# Power.net
KiCad netlist of a schematic drawn in Altium Designer
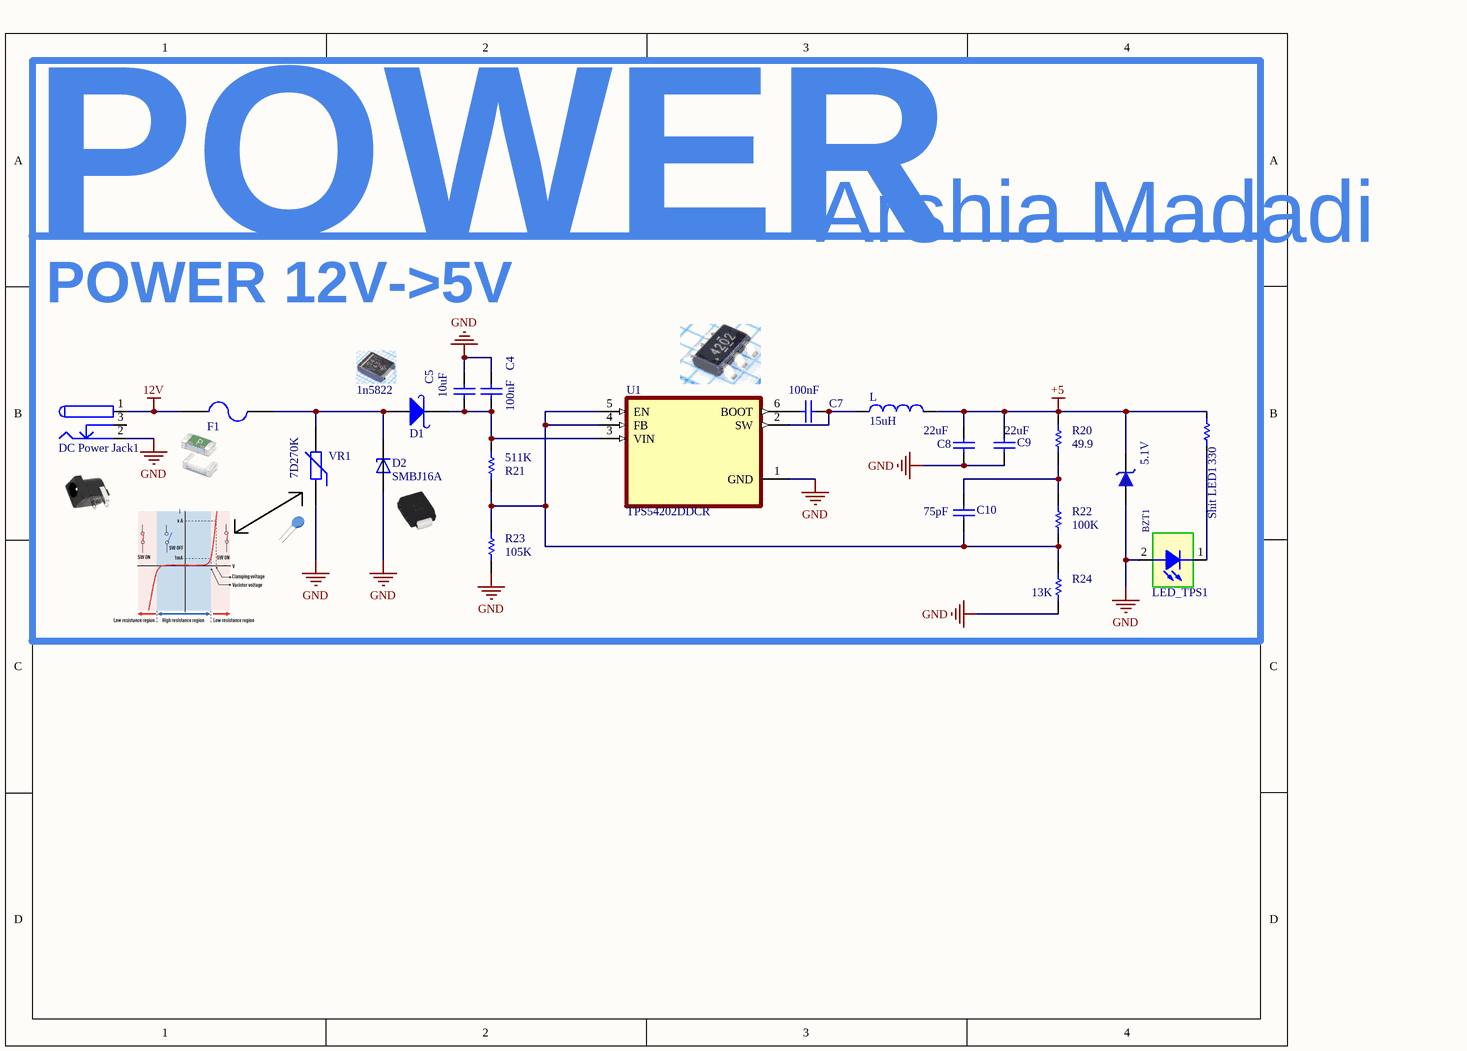
[diagram p0: Power.SchDoc]

(export (version "E")
  (design (tool "Eeschema 10.0.6"))
  (components
    (comp (ref "BZT1")
      (value "5.1V")
      (footprint "SOD123")
      (description "DIODE ZENER GENERAL")
      (fields (field (name "PUBLISHER") "Abbas Basereh"))
      (libsource (lib "Altium") (part "ZENER GENERAL DIODE"))
    )
    (comp (ref "C4")
      (value "100nF")
      (footprint "CAPC4817X12N")
      (description "CAP 1206")
      (fields (field (name "DESIGNER") "Abbas Basereh"))
      (libsource (lib "Altium") (part "CAP SMD 1206"))
    )
    (comp (ref "C5")
      (value "10uF")
      (footprint "CAPC4817X12N")
      (description "CAP 1206")
      (fields (field (name "DESIGNER") "Abbas Basereh"))
      (libsource (lib "Altium") (part "CAP SMD 1206"))
    )
    (comp (ref "C7")
      (value "100nF")
      (footprint "CAPC4817X12N")
      (description "CAP 1206")
      (fields (field (name "DESIGNER") "Abbas Basereh"))
      (libsource (lib "Altium") (part "CAP SMD 1206"))
    )
    (comp (ref "C8")
      (value "22uF")
      (footprint "CAPC4817X12N")
      (description "CAP 1206")
      (fields (field (name "DESIGNER") "Abbas Basereh"))
      (libsource (lib "Altium") (part "CAP SMD 1206"))
    )
    (comp (ref "C9")
      (value "22uF")
      (footprint "CAPC4817X12N")
      (description "CAP 1206")
      (fields (field (name "DESIGNER") "Abbas Basereh"))
      (libsource (lib "Altium") (part "CAP SMD 1206"))
    )
    (comp (ref "C10")
      (value "75pF")
      (footprint "CAPC4817X12N")
      (description "CAP 1206")
      (fields (field (name "DESIGNER") "Abbas Basereh"))
      (libsource (lib "Altium") (part "CAP SMD 1206"))
    )
    (comp (ref "D1")
      (value "1n5822")
      (footprint "DO-214AB(SMC)")
      (description "Schottky Rectifiers")
      (fields
        (field (name "MANUFACTURER") "ON Semiconductor/Fairchild")
        (field (name "DESIGNER") "Abbas Basereh")
      )
      (libsource (lib "Altium") (part "1N5822 SMD"))
    )
    (comp (ref "D2")
      (value "SMBJ16A")
      (footprint "DIOM4336X265N")
      (description "600W, 18.8V, 5%, Unidirectional, TVS")
      (fields (field (name "MF") "Taiwan Semiconductor"))
      (libsource (lib "SMBJ16A") (part "SMBJ16A"))
    )
    (comp (ref "DC Power Jack1")
      (value "DC Power Jack")
      (footprint "DC Power Jack 1")
      (description "DC Power Jack. Center Pin 2.5mm. Diameter: 5.7mm")
      (fields (field (name "DESIGNER") "Ali Hafizi"))
      (libsource (lib "Altium") (part "DC Power Jack"))
    )
    (comp (ref "F1")
      (value "F=3.0 A")
      (footprint "1206 FUSE")
      (description "SMD Fuses 1206")
      (fields (field (name "DESIGNER") "Abbas Basereh"))
      (libsource (lib "Altium") (part "Fuse SMD1206"))
    )
    (comp (ref "L")
      (value "15uH")
      (footprint "IND1206")
      (description "TOTAL INDUCTOR SMD PACK")
      (fields (field (name "DESIGNER") "Abbas Basereh"))
      (libsource (lib "Altium") (part "INDUCTOR SMD PACKAGE"))
    )
    (comp (ref "LED_TPS1")
      (value "SMD 1206 LED")
      (footprint "LED 1206")
      (libsource (lib "Altium") (part "LED SMD 1206"))
    )
    (comp (ref "R20")
      (value "49.9")
      (footprint "RESC4817X04N")
      (description "RES 1206")
      (fields (field (name "DESIGNER") "Abbas Basereh"))
      (libsource (lib "Altium") (part "RES 1206 0.25W"))
    )
    (comp (ref "R21")
      (value "511K")
      (footprint "RESC4817X04N")
      (description "RES 1206")
      (fields (field (name "DESIGNER") "Abbas Basereh"))
      (libsource (lib "Altium") (part "RES 1206 0.25W"))
    )
    (comp (ref "R22")
      (value "100K")
      (footprint "RESC4817X04N")
      (description "RES 1206")
      (fields (field (name "DESIGNER") "Abbas Basereh"))
      (libsource (lib "Altium") (part "RES 1206 0.25W"))
    )
    (comp (ref "R23")
      (value "105K")
      (footprint "RESC4817X04N")
      (description "RES 1206")
      (fields (field (name "DESIGNER") "Abbas Basereh"))
      (libsource (lib "Altium") (part "RES 1206 0.25W"))
    )
    (comp (ref "R24")
      (value "13K")
      (footprint "RESC4817X04N")
      (description "RES 1206")
      (fields (field (name "DESIGNER") "Abbas Basereh"))
      (libsource (lib "Altium") (part "RES 1206 0.25W"))
    )
    (comp (ref "Shit LED1")
      (value "330")
      (footprint "1206_Res")
      (description "Resistor")
      (fields (field (name "PUBLISHER") "Altium Limited"))
      (libsource (lib "Sajad_Altium_Library") (part "Res"))
    )
    (comp (ref "U1")
      (value "TPS54202DDCR")
      (footprint "SOT95P280X110-6N")
      (fields (field (name "MF") "Texas Instruments"))
      (libsource (lib "TPS54202DDCR (3)") (part "TPS54202DDCR"))
    )
    (comp (ref "VR1")
      (value "7D270K")
      (footprint "07D XXX")
      (description "VARISTORS")
      (fields
        (field (name "MANUFACTURER") "china-canada-philipina")
        (field (name "DESIGNER") "Abbas Basereh")
        (field (name "PUBLISHER") "ABBAS BASEREH")
      )
      (libsource (lib "Altium") (part "VARISTOR (VDR)"))
    )
  )
  (nets
    (net (code "1") (name "+5") (class "Default")
      (node (ref "BZT1") (pin "2") (pintype "passive"))
      (node (ref "C8") (pin "2") (pinfunction "2_2") (pintype "passive"))
      (node (ref "C9") (pin "2") (pinfunction "2_2") (pintype "passive"))
      (node (ref "L") (pin "2") (pinfunction "2_2") (pintype "passive"))
      (node (ref "R20") (pin "2") (pinfunction "2_2") (pintype "passive"))
      (node (ref "Shit LED1") (pin "2") (pinfunction "2_2") (pintype "passive"))
    )
    (net (code "2") (name "12V") (class "Default")
      (node (ref "DC Power Jack1") (pin "1") (pinfunction "1_1") (pintype "power_in"))
      (node (ref "F1") (pin "1") (pinfunction "1_1") (pintype "passive"))
    )
    (net (code "3") (name "GND") (class "Default")
      (node (ref "BZT1") (pin "1") (pintype "passive"))
      (node (ref "C4") (pin "2") (pinfunction "2_2") (pintype "passive"))
      (node (ref "C5") (pin "2") (pinfunction "2_2") (pintype "passive"))
      (node (ref "C8") (pin "1") (pinfunction "1_1") (pintype "passive"))
      (node (ref "C9") (pin "1") (pinfunction "1_1") (pintype "passive"))
      (node (ref "D2") (pin "A") (pinfunction "A_A") (pintype "passive"))
      (node (ref "DC Power Jack1") (pin "2") (pinfunction "2_2") (pintype "power_in"))
      (node (ref "LED_TPS1") (pin "2") (pinfunction "2_2") (pintype "passive"))
      (node (ref "R23") (pin "1") (pinfunction "1_1") (pintype "passive"))
      (node (ref "R24") (pin "1") (pinfunction "1_1") (pintype "passive"))
      (node (ref "U1") (pin "1") (pinfunction "GND_1") (pintype "power_in"))
      (node (ref "VR1") (pin "1") (pinfunction "1_1") (pintype "passive"))
    )
    (net (code "4") (name "Net-(C10-Pad2)") (class "Default")
      (node (ref "C10") (pin "2") (pinfunction "2_2") (pintype "passive"))
      (node (ref "R20") (pin "1") (pinfunction "1_1") (pintype "passive"))
      (node (ref "R22") (pin "2") (pinfunction "2_2") (pintype "passive"))
    )
    (net (code "5") (name "Net-(D1-A)") (class "Default")
      (node (ref "D1") (pin "1") (pinfunction "A_1") (pintype "passive"))
      (node (ref "D2") (pin "C") (pinfunction "C_C") (pintype "passive"))
      (node (ref "F1") (pin "2") (pinfunction "2_2") (pintype "passive"))
      (node (ref "VR1") (pin "2") (pinfunction "2_2") (pintype "passive"))
    )
    (net (code "6") (name "Net-(D1-K)") (class "Default")
      (node (ref "C4") (pin "1") (pinfunction "1_1") (pintype "passive"))
      (node (ref "C5") (pin "1") (pinfunction "1_1") (pintype "passive"))
      (node (ref "D1") (pin "2") (pinfunction "K_2") (pintype "passive"))
      (node (ref "R21") (pin "2") (pinfunction "2_2") (pintype "passive"))
      (node (ref "U1") (pin "3") (pinfunction "VIN_3") (pintype "input"))
    )
    (net (code "7") (name "Net-(LED_TPS1-Pad1)") (class "Default")
      (node (ref "LED_TPS1") (pin "1") (pinfunction "1_1") (pintype "passive"))
      (node (ref "Shit LED1") (pin "1") (pinfunction "1_1") (pintype "passive"))
    )
    (net (code "8") (name "Net-(U1-BOOT)") (class "Default")
      (node (ref "C7") (pin "1") (pinfunction "1_1") (pintype "passive"))
      (node (ref "U1") (pin "6") (pinfunction "BOOT_6") (pintype "output"))
    )
    (net (code "9") (name "Net-(U1-EN)") (class "Default")
      (node (ref "C10") (pin "1") (pinfunction "1_1") (pintype "passive"))
      (node (ref "R21") (pin "1") (pinfunction "1_1") (pintype "passive"))
      (node (ref "R22") (pin "1") (pinfunction "1_1") (pintype "passive"))
      (node (ref "R23") (pin "2") (pinfunction "2_2") (pintype "passive"))
      (node (ref "R24") (pin "2") (pinfunction "2_2") (pintype "passive"))
      (node (ref "U1") (pin "4") (pinfunction "FB_4") (pintype "input"))
      (node (ref "U1") (pin "5") (pinfunction "EN_5") (pintype "input"))
    )
    (net (code "10") (name "Net-(U1-SW)") (class "Default")
      (node (ref "C7") (pin "2") (pinfunction "2_2") (pintype "passive"))
      (node (ref "L") (pin "1") (pinfunction "1_1") (pintype "passive"))
      (node (ref "U1") (pin "2") (pinfunction "SW_2") (pintype "output"))
    )
    (net (code "11") (name "unconnected-(DC Power Jack1-Pad3)") (class "Default")
      (node (ref "DC Power Jack1") (pin "3") (pinfunction "3_3") (pintype "power_in"))
    )
  )
)
